# trigger.net
KiCad netlist of a schematic drawn in EAGLE
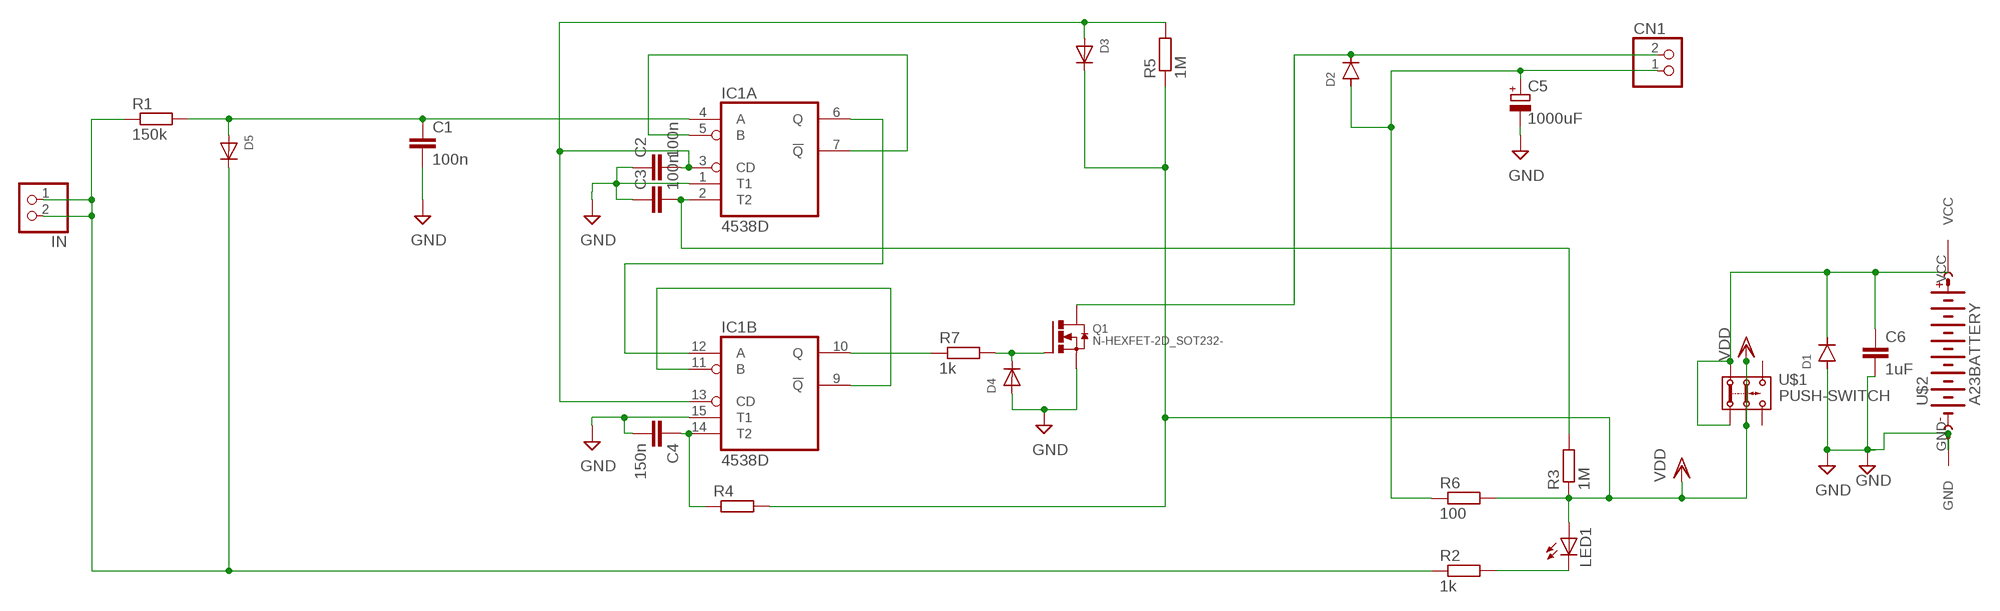
[diagram p0: schematic, sheet 1]

(export (version "E")
  (design (tool "Eeschema 10.0.6"))
  (components
    (comp (ref "C1")
      (value "100n")
      (footprint "eagle-import:C0805")
      (libsource (lib "eagle-import") (part "C"))
    )
    (comp (ref "C2")
      (value "100n")
      (footprint "eagle-import:C0805")
      (libsource (lib "eagle-import") (part "C"))
    )
    (comp (ref "C3")
      (value "100n")
      (footprint "eagle-import:C0805")
      (libsource (lib "eagle-import") (part "C"))
    )
    (comp (ref "C4")
      (value "150n")
      (footprint "eagle-import:C0805")
      (libsource (lib "eagle-import") (part "C"))
    )
    (comp (ref "C5")
      (value "1000uF")
      (footprint "eagle-import:E5-6")
      (libsource (lib "eagle-import") (part "CPOL-EUE5-6"))
    )
    (comp (ref "C6")
      (value "1uF")
      (footprint "eagle-import:C1808")
      (libsource (lib "eagle-import") (part "CC1808"))
    )
    (comp (ref "CN1")
      (value "JST_2PIN-THM")
      (footprint "eagle-import:JST-PH-2-THM")
      (libsource (lib "eagle-import") (part "JST_2PIN-THM"))
    )
    (comp (ref "D1")
      (value "D-SMB")
      (footprint "eagle-import:SMB")
      (libsource (lib "eagle-import") (part "D-SMB"))
    )
    (comp (ref "D2")
      (value "D-SMB")
      (footprint "eagle-import:SMB")
      (libsource (lib "eagle-import") (part "D-SMB"))
    )
    (comp (ref "D3")
      (value "DIODESOD-123")
      (footprint "eagle-import:SOD-123")
      (libsource (lib "eagle-import") (part "DIODESOD-123"))
    )
    (comp (ref "D4")
      (value "DIODESOD-123")
      (footprint "eagle-import:SOD-123")
      (libsource (lib "eagle-import") (part "DIODESOD-123"))
    )
    (comp (ref "D5")
      (value "DIODESOD-123")
      (footprint "eagle-import:SOD-123")
      (libsource (lib "eagle-import") (part "DIODESOD-123"))
    )
    (comp (ref "IC1")
      (value "4538D")
      (footprint "eagle-import:SO16")
      (libsource (lib "eagle-import") (part "4538D"))
    )
    (comp (ref "IN")
      (value "JST_2PIN-THM")
      (footprint "eagle-import:JST-PH-2-THM")
      (libsource (lib "eagle-import") (part "JST_2PIN-THM"))
    )
    (comp (ref "LED1")
      (value "LED3MM")
      (footprint "eagle-import:LED3MM")
      (libsource (lib "eagle-import") (part "LED3MM"))
    )
    (comp (ref "Q1")
      (value "N-HEXFET-2D_SOT232-")
      (footprint "eagle-import:SOT223")
      (libsource (lib "eagle-import") (part "N-HEXFET-2D_?-SOT232"))
    )
    (comp (ref "R1")
      (value "150k")
      (footprint "eagle-import:R1206")
      (libsource (lib "eagle-import") (part "RR1206"))
    )
    (comp (ref "R2")
      (value "1k")
      (footprint "eagle-import:R1206")
      (libsource (lib "eagle-import") (part "RR1206"))
    )
    (comp (ref "R3")
      (value "1M")
      (footprint "eagle-import:R1206")
      (libsource (lib "eagle-import") (part "RR1206"))
    )
    (comp (ref "R4")
      (value "RR1206")
      (footprint "eagle-import:R1206")
      (libsource (lib "eagle-import") (part "RR1206"))
    )
    (comp (ref "R5")
      (value "1M")
      (footprint "eagle-import:R1206")
      (libsource (lib "eagle-import") (part "RR1206"))
    )
    (comp (ref "R6")
      (value "100")
      (footprint "eagle-import:R2512")
      (libsource (lib "eagle-import") (part "RR2512"))
    )
    (comp (ref "R7")
      (value "1k")
      (footprint "eagle-import:R1206")
      (libsource (lib "eagle-import") (part "RR1206"))
    )
    (comp (ref "U$1")
      (value "PUSH-SWITCH")
      (footprint "eagle-import:PUSH-SWITCH")
      (libsource (lib "eagle-import") (part "PUSH-SWITCH"))
    )
    (comp (ref "U$2")
      (value "A23BATTERY")
      (footprint "eagle-import:A23")
      (libsource (lib "eagle-import") (part "A23BATTERY"))
    )
  )
  (nets
    (net (code "1") (name "GND") (class "Default")
      (node (ref "C1") (pin "2") (pinfunction "2_2") (pintype "passive"))
      (node (ref "C2") (pin "1") (pinfunction "1_1") (pintype "passive"))
      (node (ref "C3") (pin "1") (pinfunction "1_1") (pintype "passive"))
      (node (ref "C4") (pin "2") (pinfunction "2_2") (pintype "passive"))
      (node (ref "C5") (pin "-") (pinfunction "-_-") (pintype "passive"))
      (node (ref "C6") (pin "2") (pinfunction "2_2") (pintype "passive"))
      (node (ref "D1") (pin "2") (pinfunction "A_2") (pintype "passive"))
      (node (ref "D4") (pin "A") (pinfunction "A_A") (pintype "passive"))
      (node (ref "IC1") (pin "1") (pinfunction "T1_1") (pintype "input"))
      (node (ref "IC1") (pin "15") (pinfunction "T1_15") (pintype "input"))
      (node (ref "Q1") (pin "3") (pinfunction "S_3") (pintype "passive"))
      (node (ref "U$2") (pin "GND") (pinfunction "GND_GND") (pintype "bidirectional"))
    )
    (net (code "2") (name "Net-(CN1-1)") (class "Default")
      (node (ref "CN1") (pin "2") (pinfunction "1_2") (pintype "passive"))
      (node (ref "D2") (pin "1") (pinfunction "C_1") (pintype "passive"))
      (node (ref "Q1") (pin "2") (pinfunction "D_2") (pintype "passive"))
      (node (ref "Q1") (pin "4") (pinfunction "D_4") (pintype "passive"))
    )
    (net (code "3") (name "Net-(CN1-2)") (class "Default")
      (node (ref "C5") (pin "+") (pinfunction "+_+") (pintype "passive"))
      (node (ref "CN1") (pin "1") (pinfunction "2_1") (pintype "passive"))
      (node (ref "D2") (pin "2") (pinfunction "A_2") (pintype "passive"))
      (node (ref "R6") (pin "1") (pinfunction "1_1") (pintype "passive"))
    )
    (net (code "4") (name "Net-(D1-C)") (class "Default")
      (node (ref "C6") (pin "1") (pinfunction "1_1") (pintype "passive"))
      (node (ref "D1") (pin "1") (pinfunction "C_1") (pintype "passive"))
      (node (ref "U$1") (pin "P$1") (pinfunction "1.2_P$1") (pintype "passive"))
      (node (ref "U$1") (pin "P$5") (pinfunction "1.1_P$5") (pintype "passive"))
      (node (ref "U$2") (pin "VCC") (pinfunction "VCC_VCC") (pintype "bidirectional"))
    )
    (net (code "5") (name "Net-(IC1A-A)") (class "Default")
      (node (ref "C1") (pin "1") (pinfunction "1_1") (pintype "passive"))
      (node (ref "D5") (pin "A") (pinfunction "A_A") (pintype "passive"))
      (node (ref "IC1") (pin "4") (pinfunction "A_4") (pintype "input"))
      (node (ref "R1") (pin "2") (pinfunction "2_2") (pintype "passive"))
    )
    (net (code "6") (name "Net-(IC1A-B)") (class "Default")
      (node (ref "IC1") (pin "5") (pinfunction "B_5") (pintype "input"))
      (node (ref "IC1") (pin "7") (pinfunction "~{Q}_7") (pintype "output"))
    )
    (net (code "7") (name "Net-(IC1A-CD)") (class "Default")
      (node (ref "C2") (pin "2") (pinfunction "2_2") (pintype "passive"))
      (node (ref "D3") (pin "A") (pinfunction "A_A") (pintype "passive"))
      (node (ref "IC1") (pin "13") (pinfunction "CD_13") (pintype "input"))
      (node (ref "IC1") (pin "3") (pinfunction "CD_3") (pintype "input"))
      (node (ref "R5") (pin "2") (pinfunction "2_2") (pintype "passive"))
    )
    (net (code "8") (name "Net-(IC1A-Q)") (class "Default")
      (node (ref "IC1") (pin "12") (pinfunction "A_12") (pintype "input"))
      (node (ref "IC1") (pin "6") (pinfunction "Q_6") (pintype "output"))
    )
    (net (code "9") (name "Net-(IC1A-T2)") (class "Default")
      (node (ref "C3") (pin "2") (pinfunction "2_2") (pintype "passive"))
      (node (ref "IC1") (pin "2") (pinfunction "T2_2") (pintype "input"))
      (node (ref "R3") (pin "2") (pinfunction "2_2") (pintype "passive"))
    )
    (net (code "10") (name "Net-(IC1B-B)") (class "Default")
      (node (ref "IC1") (pin "11") (pinfunction "B_11") (pintype "input"))
      (node (ref "IC1") (pin "9") (pinfunction "~{Q}_9") (pintype "output"))
    )
    (net (code "11") (name "Net-(IC1B-Q)") (class "Default")
      (node (ref "IC1") (pin "10") (pinfunction "Q_10") (pintype "output"))
      (node (ref "R7") (pin "1") (pinfunction "1_1") (pintype "passive"))
    )
    (net (code "12") (name "Net-(IC1B-T2)") (class "Default")
      (node (ref "C4") (pin "1") (pinfunction "1_1") (pintype "passive"))
      (node (ref "IC1") (pin "14") (pinfunction "T2_14") (pintype "input"))
      (node (ref "R4") (pin "1") (pinfunction "1_1") (pintype "passive"))
    )
    (net (code "13") (name "Net-(IN-1)") (class "Default")
      (node (ref "D5") (pin "C") (pinfunction "C_C") (pintype "passive"))
      (node (ref "IN") (pin "1") (pinfunction "2_1") (pintype "passive"))
      (node (ref "IN") (pin "2") (pinfunction "1_2") (pintype "passive"))
      (node (ref "R1") (pin "1") (pinfunction "1_1") (pintype "passive"))
      (node (ref "R2") (pin "1") (pinfunction "1_1") (pintype "passive"))
    )
    (net (code "14") (name "Net-(LED1-C)") (class "Default")
      (node (ref "LED1") (pin "K") (pinfunction "C_K") (pintype "passive"))
      (node (ref "R2") (pin "2") (pinfunction "2_2") (pintype "passive"))
    )
    (net (code "15") (name "Net-(Q1-G)") (class "Default")
      (node (ref "D4") (pin "C") (pinfunction "C_C") (pintype "passive"))
      (node (ref "Q1") (pin "1") (pinfunction "G_1") (pintype "passive"))
      (node (ref "R7") (pin "2") (pinfunction "2_2") (pintype "passive"))
    )
    (net (code "16") (name "VDD") (class "Default")
      (node (ref "D3") (pin "C") (pinfunction "C_C") (pintype "passive"))
      (node (ref "LED1") (pin "A") (pinfunction "A_A") (pintype "passive"))
      (node (ref "R3") (pin "1") (pinfunction "1_1") (pintype "passive"))
      (node (ref "R4") (pin "2") (pinfunction "2_2") (pintype "passive"))
      (node (ref "R5") (pin "1") (pinfunction "1_1") (pintype "passive"))
      (node (ref "R6") (pin "2") (pinfunction "2_2") (pintype "passive"))
      (node (ref "U$1") (pin "P$2") (pinfunction "2.2_P$2") (pintype "passive"))
      (node (ref "U$1") (pin "P$6") (pinfunction "2.1_P$6") (pintype "passive"))
    )
    (net (code "17") (name "unconnected-(U$1-3.1-PadP$4)") (class "Default")
      (node (ref "U$1") (pin "P$4") (pinfunction "3.1_P$4") (pintype "passive"))
    )
    (net (code "18") (name "unconnected-(U$1-3.2-PadP$3)") (class "Default")
      (node (ref "U$1") (pin "P$3") (pinfunction "3.2_P$3") (pintype "passive"))
    )
  )
)
